# ESP32.net
KiCad netlist of a schematic drawn in Altium Designer
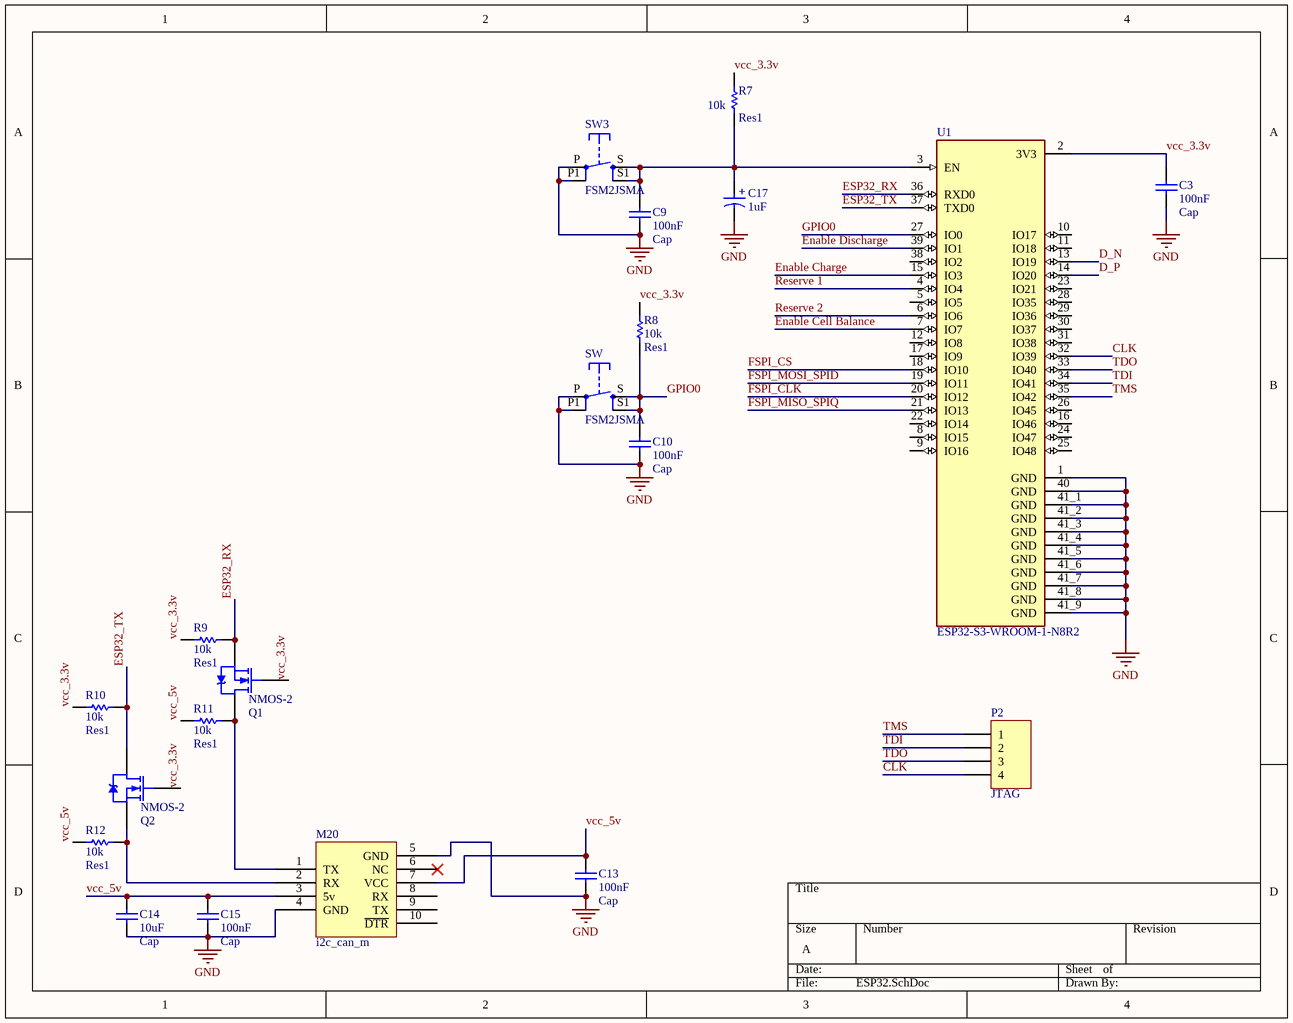
[diagram p0: ESP32.SchDoc]

(export (version "E")
  (design (tool "Eeschema 10.0.6"))
  (components
    (comp (ref "C3")
      (value "Cap")
      (footprint "6-0805_L")
      (description "Capacitor")
      (fields (field (name "ALTIUM_VALUE") "100nF") (field (name "PUBLISHER") "Altium Limited"))
      (libsource (lib "Miscellaneous Devices") (part "Cap"))
    )
    (comp (ref "C9")
      (value "Cap")
      (footprint "6-0805_L")
      (description "Capacitor")
      (fields (field (name "ALTIUM_VALUE") "100nF") (field (name "PUBLISHER") "Altium Limited"))
      (libsource (lib "Miscellaneous Devices") (part "Cap"))
    )
    (comp (ref "C10")
      (value "Cap")
      (footprint "6-0805_L")
      (description "Capacitor")
      (fields (field (name "ALTIUM_VALUE") "100nF") (field (name "PUBLISHER") "Altium Limited"))
      (libsource (lib "Miscellaneous Devices") (part "Cap"))
    )
    (comp (ref "C13")
      (value "Cap")
      (footprint "6-0805_L")
      (description "Capacitor")
      (fields (field (name "ALTIUM_VALUE") "100nF") (field (name "PUBLISHER") "Altium Limited"))
      (libsource (lib "Miscellaneous Devices") (part "Cap"))
    )
    (comp (ref "C14")
      (value "Cap")
      (footprint "6-0805_L")
      (description "Capacitor")
      (fields (field (name "ALTIUM_VALUE") "10uF") (field (name "PUBLISHER") "Altium Limited"))
      (libsource (lib "Miscellaneous Devices") (part "Cap"))
    )
    (comp (ref "C15")
      (value "Cap")
      (footprint "6-0805_L")
      (description "Capacitor")
      (fields (field (name "ALTIUM_VALUE") "100nF") (field (name "PUBLISHER") "Altium Limited"))
      (libsource (lib "Miscellaneous Devices") (part "Cap"))
    )
    (comp (ref "C17")
      (value "1uF")
      (footprint "SMB")
      (description "WCAP-ASLL Aluminum Electrolytic Capacitor, V-Chip, SMT, D6.3 x H5.5mm, 10uF, 50V")
      (fields
        (field (name "MANUFACTURER PART NUMBER") "865060643005")
        (field (name "MANUFACTURER") "Wurth Elektronik")
      )
      (libsource (lib "865060140001_Altium_WCAP-ASLL_rev24b") (part "865060643005"))
    )
    (comp (ref "M20")
      (value "i2c_can_m")
      (footprint "i2c_can_module")
      (description "i2c_can_module")
      (libsource (lib "bms_can_wifi_library") (part "i2c_can_m"))
    )
    (comp (ref "P2")
      (value "JTAG")
      (footprint "HDR1X4")
      (description "Header, 4-Pin")
      (fields (field (name "PUBLISHER") "Altium Limited"))
      (libsource (lib "Miscellaneous Connectors") (part "Header 4"))
    )
    (comp (ref "Q1")
      (value "NMOS-2")
      (footprint "SOT23_N")
      (description "N-Channel Power MOSFET")
      (fields (field (name "PUBLISHER") "Altium Limited"))
      (libsource (lib "Miscellaneous Devices") (part "NMOS-2"))
    )
    (comp (ref "Q2")
      (value "NMOS-2")
      (footprint "SOT23_N")
      (description "N-Channel Power MOSFET")
      (fields (field (name "PUBLISHER") "Altium Limited"))
      (libsource (lib "Miscellaneous Devices") (part "NMOS-2"))
    )
    (comp (ref "R7")
      (value "Res1")
      (footprint "6-0805_N")
      (description "Resistor")
      (fields (field (name "ALTIUM_VALUE") "10k") (field (name "PUBLISHER") "Altium Limited"))
      (libsource (lib "Miscellaneous Devices") (part "Res1"))
    )
    (comp (ref "R8")
      (value "Res1")
      (footprint "6-0805_N")
      (description "Resistor")
      (fields (field (name "ALTIUM_VALUE") "10k") (field (name "PUBLISHER") "Altium Limited"))
      (libsource (lib "Miscellaneous Devices") (part "Res1"))
    )
    (comp (ref "R9")
      (value "Res1")
      (footprint "6-0805_N")
      (description "Resistor")
      (fields (field (name "ALTIUM_VALUE") "10k") (field (name "PUBLISHER") "Altium Limited"))
      (libsource (lib "Miscellaneous Devices") (part "Res1"))
    )
    (comp (ref "R10")
      (value "Res1")
      (footprint "6-0805_N")
      (description "Resistor")
      (fields (field (name "ALTIUM_VALUE") "10k") (field (name "PUBLISHER") "Altium Limited"))
      (libsource (lib "Miscellaneous Devices") (part "Res1"))
    )
    (comp (ref "R11")
      (value "Res1")
      (footprint "6-0805_N")
      (description "Resistor")
      (fields (field (name "ALTIUM_VALUE") "10k") (field (name "PUBLISHER") "Altium Limited"))
      (libsource (lib "Miscellaneous Devices") (part "Res1"))
    )
    (comp (ref "R12")
      (value "Res1")
      (footprint "6-0805_N")
      (description "Resistor")
      (fields (field (name "ALTIUM_VALUE") "10k") (field (name "PUBLISHER") "Altium Limited"))
      (libsource (lib "Miscellaneous Devices") (part "Res1"))
    )
    (comp (ref "SW")
      (value "FSM2JSMA")
      (footprint "FSM2JSMA")
      (description "Tactile Switch SPST-NO Top Actuated Surface Mount")
      (fields (field (name "MF") "TE Connectivity") (field (name "MP") "FSM-2J-SMA"))
      (libsource (lib "FSM2JSMA") (part "FSM2JSMA"))
    )
    (comp (ref "SW3")
      (value "FSM2JSMA")
      (footprint "FSM2JSMA")
      (description "Tactile Switch SPST-NO Top Actuated Surface Mount")
      (fields (field (name "MF") "TE Connectivity") (field (name "MP") "FSM-2J-SMA"))
      (libsource (lib "FSM2JSMA") (part "FSM2JSMA"))
    )
    (comp (ref "U1")
      (value "ESP32-S3-WROOM-1-N8R2")
      (footprint "XCVR_ESP32-S3-WROOM-1-N8R2")
      (description "WiFi 802.11a/b/g/n, Bluetooth v5.0 Transceiver Module 2.4GHz Antenna Not Included -")
      (fields (field (name "MF") "Espressif Systems"))
      (libsource (lib "ESP32-S3-WROOM-1-N8R2") (part "ESP32-S3-WROOM-1-N8R2"))
    )
  )
  (nets
    (net (code "1") (name "/CLK") (class "Default")
      (node (ref "P2") (pin "4") (pinfunction "4_4") (pintype "passive"))
      (node (ref "U1") (pin "32") (pinfunction "IO39_32") (pintype "bidirectional"))
    )
    (net (code "2") (name "/D_N") (class "Default")
      (node (ref "U1") (pin "13") (pinfunction "IO19_13") (pintype "bidirectional"))
    )
    (net (code "3") (name "/D_P") (class "Default")
      (node (ref "U1") (pin "14") (pinfunction "IO20_14") (pintype "bidirectional"))
    )
    (net (code "4") (name "/ESP32_RX") (class "Default")
      (node (ref "Q1") (pin "3") (pinfunction "S_3") (pintype "passive"))
      (node (ref "R9") (pin "1") (pinfunction "1_1") (pintype "passive"))
      (node (ref "U1") (pin "36") (pinfunction "RXD0_36") (pintype "bidirectional"))
    )
    (net (code "5") (name "/ESP32_TX") (class "Default")
      (node (ref "Q2") (pin "2") (pinfunction "D_2") (pintype "passive"))
      (node (ref "R10") (pin "2") (pinfunction "2_2") (pintype "passive"))
      (node (ref "U1") (pin "37") (pinfunction "TXD0_37") (pintype "bidirectional"))
    )
    (net (code "6") (name "/Enable Cell Balance") (class "Default")
      (node (ref "U1") (pin "7") (pinfunction "IO7_7") (pintype "bidirectional"))
    )
    (net (code "7") (name "/Enable Charge") (class "Default")
      (node (ref "U1") (pin "15") (pinfunction "IO3_15") (pintype "bidirectional"))
    )
    (net (code "8") (name "/Enable Discharge") (class "Default")
      (node (ref "U1") (pin "39") (pinfunction "IO1_39") (pintype "bidirectional"))
    )
    (net (code "9") (name "/FSPI_CLK") (class "Default")
      (node (ref "U1") (pin "20") (pinfunction "IO12_20") (pintype "bidirectional"))
    )
    (net (code "10") (name "/FSPI_CS") (class "Default")
      (node (ref "U1") (pin "18") (pinfunction "IO10_18") (pintype "bidirectional"))
    )
    (net (code "11") (name "/FSPI_MISO_SPIQ") (class "Default")
      (node (ref "U1") (pin "21") (pinfunction "IO13_21") (pintype "bidirectional"))
    )
    (net (code "12") (name "/FSPI_MOSI_SPID") (class "Default")
      (node (ref "U1") (pin "19") (pinfunction "IO11_19") (pintype "bidirectional"))
    )
    (net (code "13") (name "/GPIO0") (class "Default")
      (node (ref "C10") (pin "2") (pinfunction "2_2") (pintype "passive"))
      (node (ref "R8") (pin "1") (pinfunction "1_1") (pintype "passive"))
      (node (ref "SW") (pin "S") (pinfunction "S_S") (pintype "passive"))
      (node (ref "SW") (pin "S1") (pinfunction "S@1_S1") (pintype "passive"))
      (node (ref "U1") (pin "27") (pinfunction "IO0_27") (pintype "bidirectional"))
    )
    (net (code "14") (name "/Reserve 1") (class "Default")
      (node (ref "U1") (pin "4") (pinfunction "IO4_4") (pintype "bidirectional"))
    )
    (net (code "15") (name "/Reserve 2") (class "Default")
      (node (ref "U1") (pin "6") (pinfunction "IO6_6") (pintype "bidirectional"))
    )
    (net (code "16") (name "/TDI") (class "Default")
      (node (ref "P2") (pin "2") (pinfunction "2_2") (pintype "passive"))
      (node (ref "U1") (pin "34") (pinfunction "IO41_34") (pintype "bidirectional"))
    )
    (net (code "17") (name "/TDO") (class "Default")
      (node (ref "P2") (pin "3") (pinfunction "3_3") (pintype "passive"))
      (node (ref "U1") (pin "33") (pinfunction "IO40_33") (pintype "bidirectional"))
    )
    (net (code "18") (name "/TMS") (class "Default")
      (node (ref "P2") (pin "1") (pinfunction "1_1") (pintype "passive"))
      (node (ref "U1") (pin "35") (pinfunction "IO42_35") (pintype "bidirectional"))
    )
    (net (code "19") (name "/vcc_3.3v") (class "Default")
      (node (ref "C3") (pin "2") (pinfunction "2_2") (pintype "passive"))
      (node (ref "Q1") (pin "1") (pinfunction "G_1") (pintype "passive"))
      (node (ref "Q2") (pin "1") (pinfunction "G_1") (pintype "passive"))
      (node (ref "R10") (pin "1") (pinfunction "1_1") (pintype "passive"))
      (node (ref "R7") (pin "2") (pinfunction "2_2") (pintype "passive"))
      (node (ref "R8") (pin "2") (pinfunction "2_2") (pintype "passive"))
      (node (ref "R9") (pin "2") (pinfunction "2_2") (pintype "passive"))
      (node (ref "U1") (pin "2") (pinfunction "3V3_2") (pintype "power_in"))
    )
    (net (code "20") (name "/vcc_5v") (class "Default")
      (node (ref "C13") (pin "2") (pinfunction "2_2") (pintype "passive"))
      (node (ref "C14") (pin "2") (pinfunction "2_2") (pintype "passive"))
      (node (ref "C15") (pin "2") (pinfunction "2_2") (pintype "passive"))
      (node (ref "M20") (pin "3") (pinfunction "5v_3") (pintype "passive"))
      (node (ref "M20") (pin "7") (pinfunction "VCC_7") (pintype "passive"))
      (node (ref "R11") (pin "1") (pinfunction "1_1") (pintype "passive"))
      (node (ref "R12") (pin "1") (pinfunction "1_1") (pintype "passive"))
    )
    (net (code "21") (name "GND") (class "Default")
      (node (ref "C10") (pin "1") (pinfunction "1_1") (pintype "passive"))
      (node (ref "C13") (pin "1") (pinfunction "1_1") (pintype "passive"))
      (node (ref "C14") (pin "1") (pinfunction "1_1") (pintype "passive"))
      (node (ref "C15") (pin "1") (pinfunction "1_1") (pintype "passive"))
      (node (ref "C17") (pin "2") (pinfunction "N_2") (pintype "passive"))
      (node (ref "C3") (pin "1") (pinfunction "1_1") (pintype "passive"))
      (node (ref "C9") (pin "1") (pinfunction "1_1") (pintype "passive"))
      (node (ref "M20") (pin "4") (pinfunction "GND_4") (pintype "passive"))
      (node (ref "M20") (pin "5") (pinfunction "GND_5") (pintype "passive"))
      (node (ref "SW") (pin "P") (pinfunction "P_P") (pintype "passive"))
      (node (ref "SW") (pin "P1") (pinfunction "P@1_P1") (pintype "passive"))
      (node (ref "SW3") (pin "P") (pinfunction "P_P") (pintype "passive"))
      (node (ref "SW3") (pin "P1") (pinfunction "P@1_P1") (pintype "passive"))
      (node (ref "U1") (pin "1") (pinfunction "GND_1") (pintype "power_in"))
      (node (ref "U1") (pin "40") (pinfunction "GND_40") (pintype "power_in"))
      (node (ref "U1") (pin "41_1") (pinfunction "GND_41_1") (pintype "power_in"))
      (node (ref "U1") (pin "41_2") (pinfunction "GND_41_2") (pintype "power_in"))
      (node (ref "U1") (pin "41_3") (pinfunction "GND_41_3") (pintype "power_in"))
      (node (ref "U1") (pin "41_4") (pinfunction "GND_41_4") (pintype "power_in"))
      (node (ref "U1") (pin "41_5") (pinfunction "GND_41_5") (pintype "power_in"))
      (node (ref "U1") (pin "41_6") (pinfunction "GND_41_6") (pintype "power_in"))
      (node (ref "U1") (pin "41_7") (pinfunction "GND_41_7") (pintype "power_in"))
      (node (ref "U1") (pin "41_8") (pinfunction "GND_41_8") (pintype "power_in"))
      (node (ref "U1") (pin "41_9") (pinfunction "GND_41_9") (pintype "power_in"))
    )
    (net (code "22") (name "Net-(C17-P)") (class "Default")
      (node (ref "C17") (pin "1") (pinfunction "P_1") (pintype "passive"))
      (node (ref "C9") (pin "2") (pinfunction "2_2") (pintype "passive"))
      (node (ref "R7") (pin "1") (pinfunction "1_1") (pintype "passive"))
      (node (ref "SW3") (pin "S") (pinfunction "S_S") (pintype "passive"))
      (node (ref "SW3") (pin "S1") (pinfunction "S@1_S1") (pintype "passive"))
      (node (ref "U1") (pin "3") (pinfunction "EN_3") (pintype "input"))
    )
    (net (code "23") (name "Net-(Q1-D)") (class "Default")
      (node (ref "M20") (pin "1") (pinfunction "TX_1") (pintype "passive"))
      (node (ref "Q1") (pin "2") (pinfunction "D_2") (pintype "passive"))
      (node (ref "R11") (pin "2") (pinfunction "2_2") (pintype "passive"))
    )
    (net (code "24") (name "Net-(Q2-S)") (class "Default")
      (node (ref "M20") (pin "2") (pinfunction "RX_2") (pintype "passive"))
      (node (ref "Q2") (pin "3") (pinfunction "S_3") (pintype "passive"))
      (node (ref "R12") (pin "2") (pinfunction "2_2") (pintype "passive"))
    )
    (net (code "25") (name "unconnected-(M20-NC-Pad6)") (class "Default")
      (node (ref "M20") (pin "6") (pinfunction "NC_6") (pintype "passive+no_connect"))
    )
    (net (code "26") (name "unconnected-(M20-RX-Pad8)") (class "Default")
      (node (ref "M20") (pin "8") (pinfunction "RX_8") (pintype "passive"))
    )
    (net (code "27") (name "unconnected-(M20-TX-Pad9)") (class "Default")
      (node (ref "M20") (pin "9") (pinfunction "TX_9") (pintype "passive"))
    )
    (net (code "28") (name "unconnected-(M20-~{DTR}-Pad10)") (class "Default")
      (node (ref "M20") (pin "10") (pinfunction "~{DTR}_10") (pintype "passive"))
    )
    (net (code "29") (name "unconnected-(U1-IO2-Pad38)") (class "Default")
      (node (ref "U1") (pin "38") (pinfunction "IO2_38") (pintype "bidirectional"))
    )
    (net (code "30") (name "unconnected-(U1-IO5-Pad5)") (class "Default")
      (node (ref "U1") (pin "5") (pinfunction "IO5_5") (pintype "bidirectional"))
    )
    (net (code "31") (name "unconnected-(U1-IO8-Pad12)") (class "Default")
      (node (ref "U1") (pin "12") (pinfunction "IO8_12") (pintype "bidirectional"))
    )
    (net (code "32") (name "unconnected-(U1-IO9-Pad17)") (class "Default")
      (node (ref "U1") (pin "17") (pinfunction "IO9_17") (pintype "bidirectional"))
    )
    (net (code "33") (name "unconnected-(U1-IO14-Pad22)") (class "Default")
      (node (ref "U1") (pin "22") (pinfunction "IO14_22") (pintype "bidirectional"))
    )
    (net (code "34") (name "unconnected-(U1-IO15-Pad8)") (class "Default")
      (node (ref "U1") (pin "8") (pinfunction "IO15_8") (pintype "bidirectional"))
    )
    (net (code "35") (name "unconnected-(U1-IO16-Pad9)") (class "Default")
      (node (ref "U1") (pin "9") (pinfunction "IO16_9") (pintype "bidirectional"))
    )
    (net (code "36") (name "unconnected-(U1-IO17-Pad10)") (class "Default")
      (node (ref "U1") (pin "10") (pinfunction "IO17_10") (pintype "bidirectional"))
    )
    (net (code "37") (name "unconnected-(U1-IO18-Pad11)") (class "Default")
      (node (ref "U1") (pin "11") (pinfunction "IO18_11") (pintype "bidirectional"))
    )
    (net (code "38") (name "unconnected-(U1-IO21-Pad23)") (class "Default")
      (node (ref "U1") (pin "23") (pinfunction "IO21_23") (pintype "bidirectional"))
    )
    (net (code "39") (name "unconnected-(U1-IO35-Pad28)") (class "Default")
      (node (ref "U1") (pin "28") (pinfunction "IO35_28") (pintype "bidirectional"))
    )
    (net (code "40") (name "unconnected-(U1-IO36-Pad29)") (class "Default")
      (node (ref "U1") (pin "29") (pinfunction "IO36_29") (pintype "bidirectional"))
    )
    (net (code "41") (name "unconnected-(U1-IO37-Pad30)") (class "Default")
      (node (ref "U1") (pin "30") (pinfunction "IO37_30") (pintype "bidirectional"))
    )
    (net (code "42") (name "unconnected-(U1-IO38-Pad31)") (class "Default")
      (node (ref "U1") (pin "31") (pinfunction "IO38_31") (pintype "bidirectional"))
    )
    (net (code "43") (name "unconnected-(U1-IO45-Pad26)") (class "Default")
      (node (ref "U1") (pin "26") (pinfunction "IO45_26") (pintype "bidirectional"))
    )
    (net (code "44") (name "unconnected-(U1-IO46-Pad16)") (class "Default")
      (node (ref "U1") (pin "16") (pinfunction "IO46_16") (pintype "bidirectional"))
    )
    (net (code "45") (name "unconnected-(U1-IO47-Pad24)") (class "Default")
      (node (ref "U1") (pin "24") (pinfunction "IO47_24") (pintype "bidirectional"))
    )
    (net (code "46") (name "unconnected-(U1-IO48-Pad25)") (class "Default")
      (node (ref "U1") (pin "25") (pinfunction "IO48_25") (pintype "bidirectional"))
    )
  )
)
